# V01.net
KiCad netlist of a schematic drawn in Altium Designer
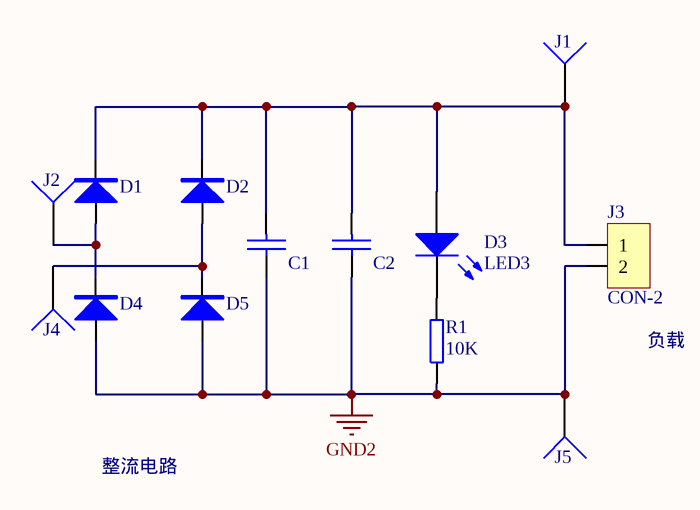
[diagram p0: 接收端V01.SchDoc]

(export (version "E")
  (design (tool "Eeschema 10.0.6"))
  (components
    (comp (ref "C1") (value "0.1uF/160V") (footprint "C1020") (libsource (lib "WegeV1") (part "CAP")))
    (comp (ref "C2") (value "0.1uF/160V") (footprint "C1020") (libsource (lib "WegeV1") (part "CAP")))
    (comp (ref "D1")
      (value "DPG30C400HB")
      (footprint "DO-41")
      (description "1N4148WS IN4148 0805 SOD323 丝印T4 贴片开关二极管")
      (libsource (lib "WegeV1") (part "1N4148"))
    )
    (comp (ref "D2")
      (value "1N4148WS")
      (footprint "DO-41")
      (description "1N4148WS IN4148 0805 SOD323 丝印T4 贴片开关二极管")
      (libsource (lib "WegeV1") (part "1N4148"))
    )
    (comp (ref "D3")
      (value "LED3")
      (footprint "3.5X2.8X1.9")
      (description "Typical BLUE SiC LED")
      (fields (field (name "PUBLISHER") "Altium Limited"))
      (libsource (lib "Miscellaneous Devices") (part "LED3"))
    )
    (comp (ref "D4")
      (value "1N4148WS")
      (footprint "DO-41")
      (description "1N4148WS IN4148 0805 SOD323 丝印T4 贴片开关二极管")
      (libsource (lib "WegeV1") (part "1N4148"))
    )
    (comp (ref "D5")
      (value "1N4148WS")
      (footprint "DO-41")
      (description "1N4148WS IN4148 0805 SOD323 丝印T4 贴片开关二极管")
      (libsource (lib "WegeV1") (part "1N4148"))
    )
    (comp (ref "J1")
      (value "Socket")
      (footprint "JET")
      (fields (field (name "PUBLISHER") "Altium Limited"))
      (libsource (lib "Miscellaneous Connectors") (part "Socket"))
    )
    (comp (ref "J2")
      (value "Socket")
      (footprint "JET")
      (fields (field (name "PUBLISHER") "Altium Limited"))
      (libsource (lib "Miscellaneous Connectors") (part "Socket"))
    )
    (comp (ref "J3") (value "CON-2") (footprint "F396P2-1") (libsource (lib "WegeV1") (part "CON-2")))
    (comp (ref "J4")
      (value "Socket")
      (footprint "JET")
      (fields (field (name "PUBLISHER") "Altium Limited"))
      (libsource (lib "Miscellaneous Connectors") (part "Socket"))
    )
    (comp (ref "J5")
      (value "Socket")
      (footprint "JET")
      (fields (field (name "PUBLISHER") "Altium Limited"))
      (libsource (lib "Miscellaneous Connectors") (part "Socket"))
    )
    (comp (ref "R1") (value "10K") (footprint "1206_R") (libsource (lib "WegeV1") (part "RES")))
  )
  (nets
    (net (code "1") (name "GND2") (class "Default")
      (node (ref "C1") (pin "2") (pinfunction "2_2") (pintype "passive"))
      (node (ref "C2") (pin "2") (pinfunction "2_2") (pintype "passive"))
      (node (ref "D4") (pin "1") (pinfunction "A_1") (pintype "passive"))
      (node (ref "D5") (pin "1") (pinfunction "A_1") (pintype "passive"))
      (node (ref "J3") (pin "2") (pinfunction "2_2") (pintype "passive"))
      (node (ref "J5") (pin "1") (pinfunction "1_1") (pintype "passive"))
      (node (ref "R1") (pin "1") (pinfunction "1_1") (pintype "passive"))
    )
    (net (code "2") (name "Net-(D1-A)") (class "Default")
      (node (ref "D1") (pin "1") (pinfunction "A_1") (pintype "passive"))
      (node (ref "D4") (pin "2") (pinfunction "K_2") (pintype "passive"))
      (node (ref "J2") (pin "1") (pinfunction "1_1") (pintype "passive"))
    )
    (net (code "3") (name "Net-(D1-K)") (class "Default")
      (node (ref "C1") (pin "1") (pinfunction "1_1") (pintype "passive"))
      (node (ref "C2") (pin "1") (pinfunction "1_1") (pintype "passive"))
      (node (ref "D1") (pin "2") (pinfunction "K_2") (pintype "passive"))
      (node (ref "D2") (pin "2") (pinfunction "K_2") (pintype "passive"))
      (node (ref "D3") (pin "1") (pinfunction "A_1") (pintype "passive"))
      (node (ref "J1") (pin "1") (pinfunction "1_1") (pintype "passive"))
      (node (ref "J3") (pin "1") (pinfunction "1_1") (pintype "passive"))
    )
    (net (code "4") (name "Net-(D2-A)") (class "Default")
      (node (ref "D2") (pin "1") (pinfunction "A_1") (pintype "passive"))
      (node (ref "D5") (pin "2") (pinfunction "K_2") (pintype "passive"))
      (node (ref "J4") (pin "1") (pinfunction "1_1") (pintype "passive"))
    )
    (net (code "5") (name "Net-(D3-K)") (class "Default")
      (node (ref "D3") (pin "2") (pinfunction "K_2") (pintype "passive"))
      (node (ref "R1") (pin "2") (pinfunction "2_2") (pintype "passive"))
    )
  )
)
